# uC.net
KiCad netlist of a schematic drawn in Altium Designer
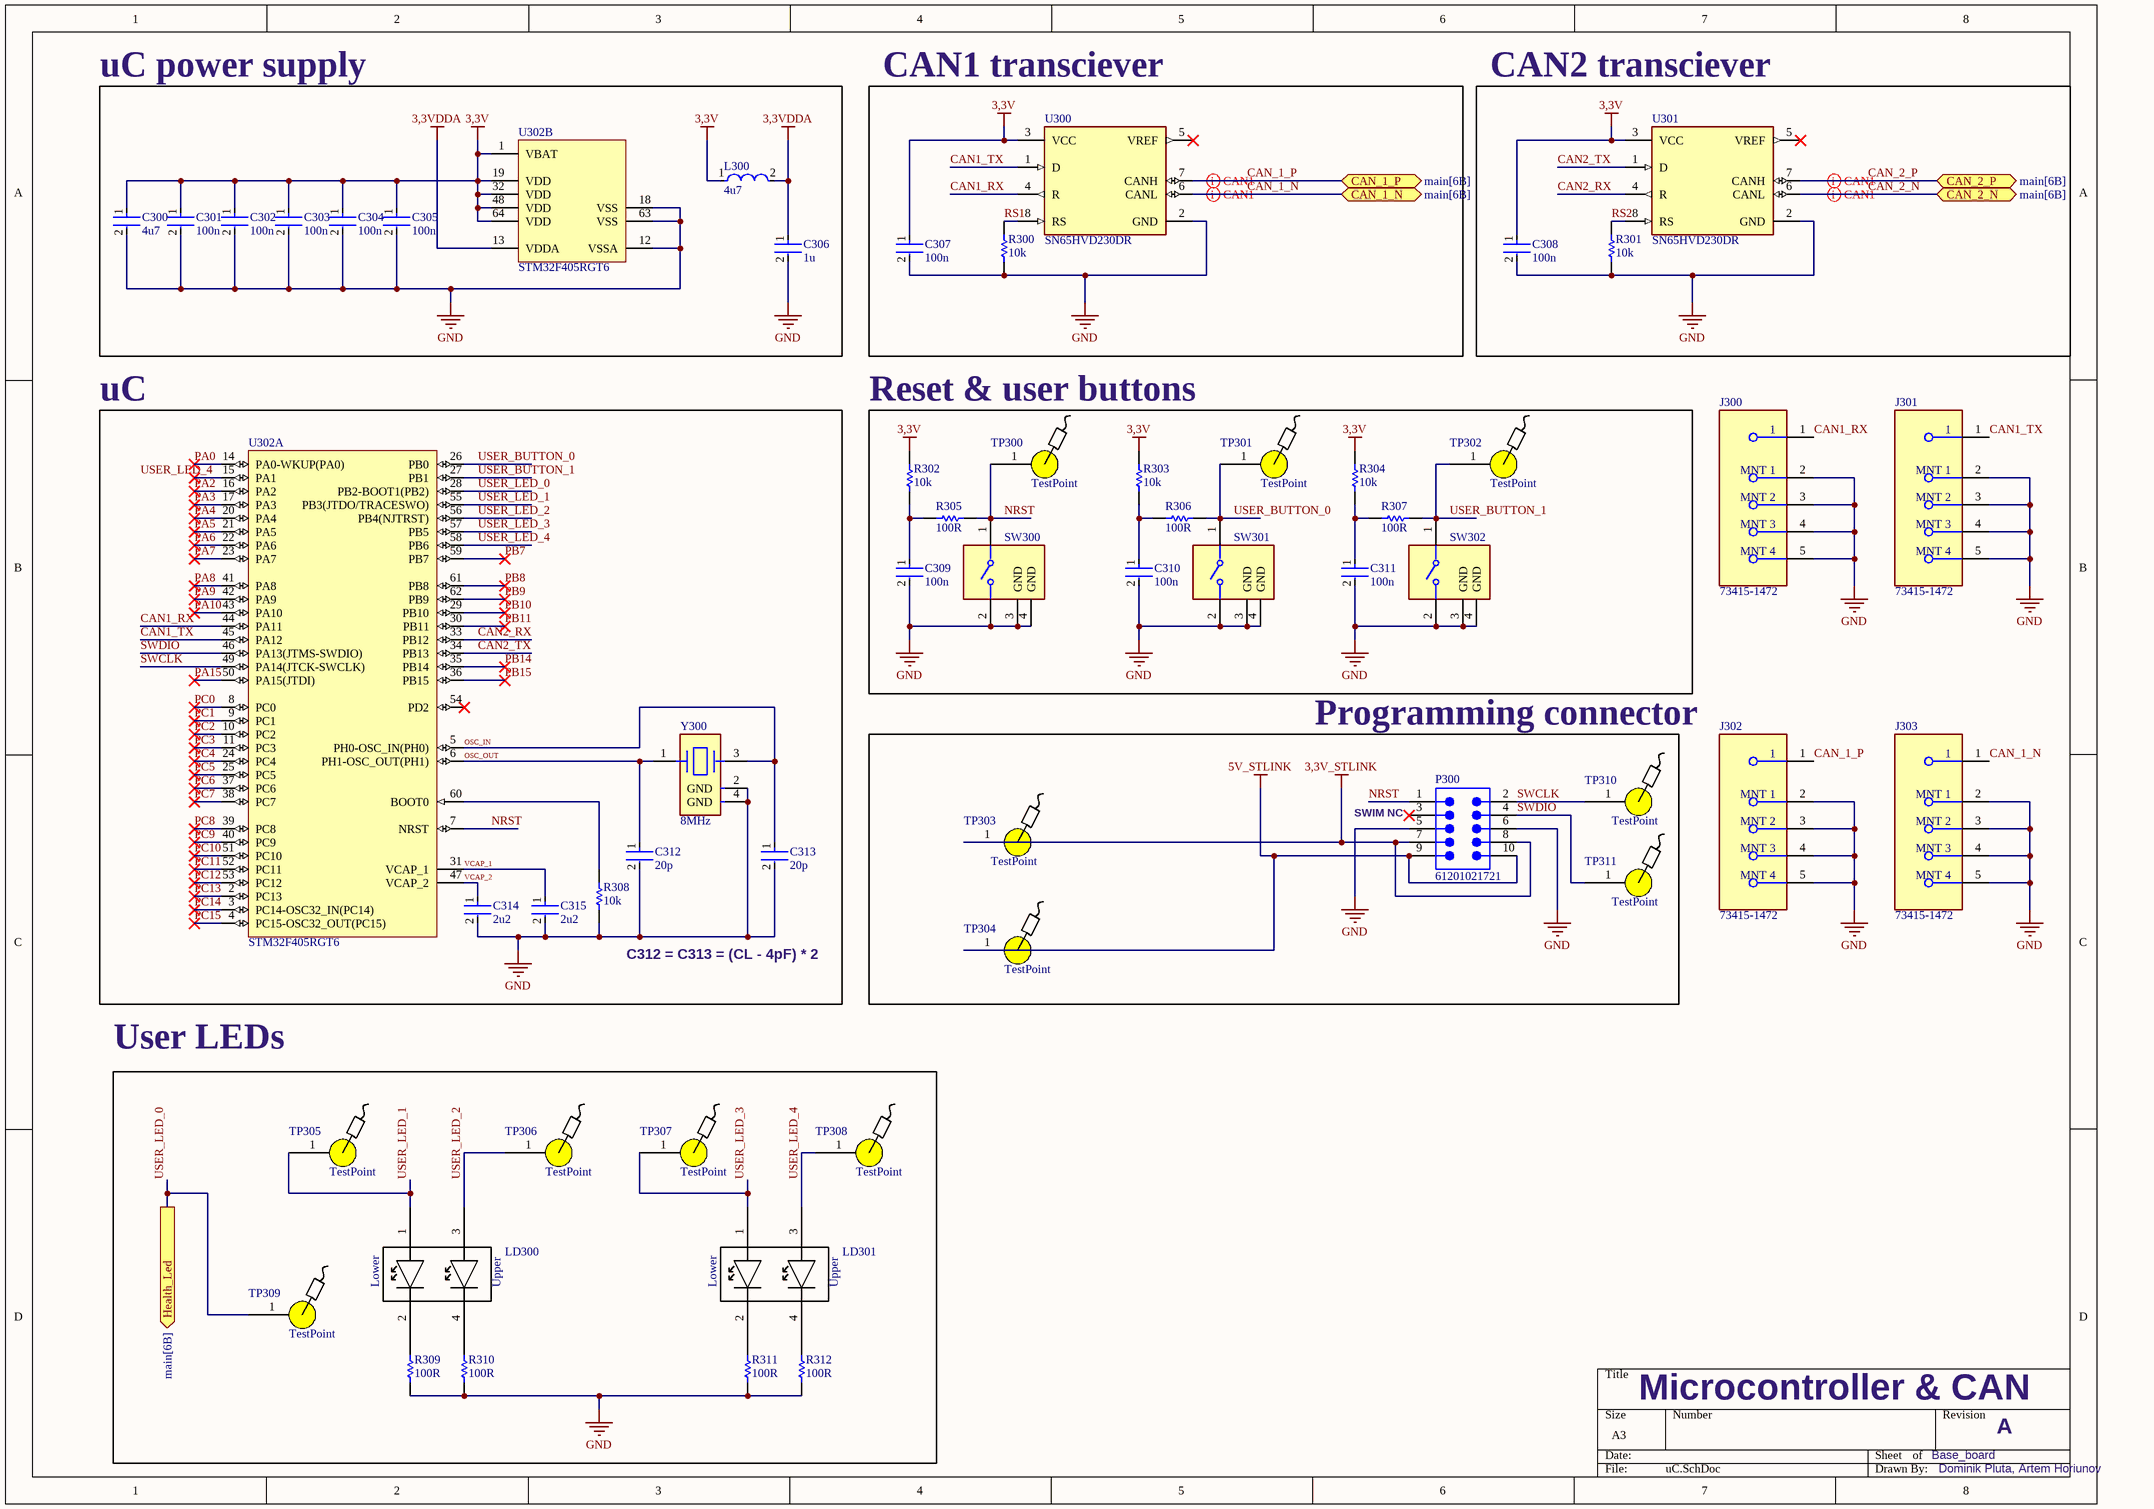
[diagram p0: uC.SchDoc]

(export (version "E")
  (design (tool "Eeschema 10.0.6"))
  (components
    (comp (ref "C300")
      (value "4u7")
      (footprint "FP-C0603C-CF-MFG")
      (description "CAP CER 0.1UF 50V X7R 0603")
      (fields (field (name "TOLERANCE") "0.1") (field (name "MANUFACTURER") "KEMET"))
      (libsource (lib "Altium Content Vault") (part "b4654b650e69147ec39a6b967a45e02"))
    )
    (comp (ref "C301")
      (value "100n")
      (footprint "FP-C0603C-CF-MFG")
      (description "CAP CER 0.1UF 50V X7R 0603")
      (fields (field (name "TOLERANCE") "0.1") (field (name "MANUFACTURER") "KEMET"))
      (libsource (lib "Altium Content Vault") (part "b4654b650e69147ec39a6b967a45e02"))
    )
    (comp (ref "C302")
      (value "100n")
      (footprint "FP-C0603C-CF-MFG")
      (description "CAP CER 0.1UF 50V X7R 0603")
      (fields (field (name "TOLERANCE") "0.1") (field (name "MANUFACTURER") "KEMET"))
      (libsource (lib "Altium Content Vault") (part "b4654b650e69147ec39a6b967a45e02"))
    )
    (comp (ref "C303")
      (value "100n")
      (footprint "FP-C0603C-CF-MFG")
      (description "CAP CER 0.1UF 50V X7R 0603")
      (fields (field (name "TOLERANCE") "0.1") (field (name "MANUFACTURER") "KEMET"))
      (libsource (lib "Altium Content Vault") (part "b4654b650e69147ec39a6b967a45e02"))
    )
    (comp (ref "C304")
      (value "100n")
      (footprint "FP-C0603C-CF-MFG")
      (description "CAP CER 0.1UF 50V X7R 0603")
      (fields (field (name "TOLERANCE") "0.1") (field (name "MANUFACTURER") "KEMET"))
      (libsource (lib "Altium Content Vault") (part "b4654b650e69147ec39a6b967a45e02"))
    )
    (comp (ref "C305")
      (value "100n")
      (footprint "FP-C0603C-CF-MFG")
      (description "CAP CER 0.1UF 50V X7R 0603")
      (fields (field (name "TOLERANCE") "0.1") (field (name "MANUFACTURER") "KEMET"))
      (libsource (lib "Altium Content Vault") (part "b4654b650e69147ec39a6b967a45e02"))
    )
    (comp (ref "C306")
      (value "1u")
      (footprint "FP-C0603C-CF-MFG")
      (description "CAP CER 0.1UF 50V X7R 0603")
      (fields (field (name "TOLERANCE") "0.1") (field (name "MANUFACTURER") "KEMET"))
      (libsource (lib "Altium Content Vault") (part "b4654b650e69147ec39a6b967a45e02"))
    )
    (comp (ref "C307")
      (value "100n")
      (footprint "FP-C0603C-CF-MFG")
      (description "CAP CER 0.1UF 50V X7R 0603")
      (fields (field (name "TOLERANCE") "0.1") (field (name "MANUFACTURER") "KEMET"))
      (libsource (lib "Altium Content Vault") (part "b4654b650e69147ec39a6b967a45e02"))
    )
    (comp (ref "C308")
      (value "100n")
      (footprint "FP-C0603C-CF-MFG")
      (description "CAP CER 0.1UF 50V X7R 0603")
      (fields (field (name "TOLERANCE") "0.1") (field (name "MANUFACTURER") "KEMET"))
      (libsource (lib "Altium Content Vault") (part "b4654b650e69147ec39a6b967a45e02"))
    )
    (comp (ref "C309")
      (value "100n")
      (footprint "FP-C0603C-CF-MFG")
      (description "CAP CER 0.1UF 50V X7R 0603")
      (fields (field (name "TOLERANCE") "0.1") (field (name "MANUFACTURER") "KEMET"))
      (libsource (lib "Altium Content Vault") (part "b4654b650e69147ec39a6b967a45e02"))
    )
    (comp (ref "C310")
      (value "100n")
      (footprint "FP-C0603C-CF-MFG")
      (description "CAP CER 0.1UF 50V X7R 0603")
      (fields (field (name "TOLERANCE") "0.1") (field (name "MANUFACTURER") "KEMET"))
      (libsource (lib "Altium Content Vault") (part "b4654b650e69147ec39a6b967a45e02"))
    )
    (comp (ref "C311")
      (value "100n")
      (footprint "FP-C0603C-CF-MFG")
      (description "CAP CER 0.1UF 50V X7R 0603")
      (fields (field (name "TOLERANCE") "0.1") (field (name "MANUFACTURER") "KEMET"))
      (libsource (lib "Altium Content Vault") (part "b4654b650e69147ec39a6b967a45e02"))
    )
    (comp (ref "C312")
      (value "20p")
      (footprint "FP-C0603C-CF-MFG")
      (description "CAP CER 50V X7R 0603")
      (fields (field (name "TOLERANCE") "0.1") (field (name "MANUFACTURER") "KEMET"))
      (libsource (lib "Altium Content Vault") (part "b4654b650e69147ec39a6b967a45e02"))
    )
    (comp (ref "C313")
      (value "20p")
      (footprint "FP-C0603C-CF-MFG")
      (description "CAP CER 50V X7R 0603")
      (fields (field (name "TOLERANCE") "0.1") (field (name "MANUFACTURER") "KEMET"))
      (libsource (lib "Altium Content Vault") (part "b4654b650e69147ec39a6b967a45e02"))
    )
    (comp (ref "C314")
      (value "2u2")
      (footprint "FP-C0603C-CF-MFG")
      (description "CAP CER 50V X7R 0603")
      (fields (field (name "TOLERANCE") "0.1") (field (name "MANUFACTURER") "KEMET"))
      (libsource (lib "Altium Content Vault") (part "b4654b650e69147ec39a6b967a45e02"))
    )
    (comp (ref "C315")
      (value "2u2")
      (footprint "FP-C0603C-CF-MFG")
      (description "CAP CER 50V X7R 0603")
      (fields (field (name "TOLERANCE") "0.1") (field (name "MANUFACTURER") "KEMET"))
      (libsource (lib "Altium Content Vault") (part "b4654b650e69147ec39a6b967a45e02"))
    )
    (comp (ref "J300")
      (value "73415-1472")
      (footprint "FP-73415-1472-MFG")
      (libsource (lib "Altium Content Vault") (part "c65b8a639cdaef1819ea20b5466f8fa"))
    )
    (comp (ref "J301")
      (value "73415-1472")
      (footprint "FP-73415-1472-MFG")
      (libsource (lib "Altium Content Vault") (part "c65b8a639cdaef1819ea20b5466f8fa"))
    )
    (comp (ref "J302")
      (value "73415-1472")
      (footprint "FP-73415-1472-MFG")
      (libsource (lib "Altium Content Vault") (part "c65b8a639cdaef1819ea20b5466f8fa"))
    )
    (comp (ref "J303")
      (value "73415-1472")
      (footprint "FP-73415-1472-MFG")
      (libsource (lib "Altium Content Vault") (part "c65b8a639cdaef1819ea20b5466f8fa"))
    )
    (comp (ref "L300")
      (value "4u7")
      (footprint "FP-LQM21DN_00-MFG")
      (description "Multilayer Type Inductor for General Circuits, 0805 (2012), 0.22μH, 10%, 0.38Ω, 250mA")
      (fields (field (name "TOLERANCE") "10%"))
      (libsource (lib "Altium Content Vault") (part "725321dda6339637d4d059423bc1c3c"))
    )
    (comp (ref "LD300")
      (value "~")
      (footprint "LedHolder:LED_HOLDER")
      (libsource (lib "LedHolder") (part "DoubleStack_Side_Led_3mm"))
    )
    (comp (ref "LD301")
      (value "~")
      (footprint "LedHolder:LED_HOLDER")
      (libsource (lib "LedHolder") (part "DoubleStack_Side_Led_3mm"))
    )
    (comp (ref "P300")
      (value "61201021721")
      (footprint "61201021721")
      (libsource (lib "Altium Content Vault") (part "Header_Male_2R_10P"))
    )
    (comp (ref "R300")
      (value "10k")
      (footprint "RESC0603(1608)_N")
      (description "2K 0.1W 5% 0603 (1608 Metric)  SMD")
      (fields (field (name "TOLERANCE") "5 %") (field (name "POWER") "0.1 W"))
      (libsource (lib "Altium Content Vault") (part "RES"))
    )
    (comp (ref "R301")
      (value "10k")
      (footprint "RESC0603(1608)_N")
      (description "2K 0.1W 5% 0603 (1608 Metric)  SMD")
      (fields (field (name "TOLERANCE") "5 %") (field (name "POWER") "0.1 W"))
      (libsource (lib "Altium Content Vault") (part "RES"))
    )
    (comp (ref "R302")
      (value "10k")
      (footprint "RESC0603(1608)_N")
      (description "0.1W 5% 0603 (1608 Metric)  SMD")
      (fields (field (name "TOLERANCE") "5 %") (field (name "POWER") "0.1 W"))
      (libsource (lib "Altium Content Vault") (part "RES"))
    )
    (comp (ref "R303")
      (value "10k")
      (footprint "RESC0603(1608)_N")
      (description "0.1W 5% 0603 (1608 Metric)  SMD")
      (fields (field (name "TOLERANCE") "5 %") (field (name "POWER") "0.1 W"))
      (libsource (lib "Altium Content Vault") (part "RES"))
    )
    (comp (ref "R304")
      (value "10k")
      (footprint "RESC0603(1608)_N")
      (description "0.1W 5% 0603 (1608 Metric)  SMD")
      (fields (field (name "TOLERANCE") "5 %") (field (name "POWER") "0.1 W"))
      (libsource (lib "Altium Content Vault") (part "RES"))
    )
    (comp (ref "R305")
      (value "100R")
      (footprint "RESC0603(1608)_N")
      (description "0.1W 5% 0603 (1608 Metric)  SMD")
      (fields (field (name "TOLERANCE") "5 %") (field (name "POWER") "0.1 W"))
      (libsource (lib "Altium Content Vault") (part "RES"))
    )
    (comp (ref "R306")
      (value "100R")
      (footprint "RESC0603(1608)_N")
      (description "0.1W 5% 0603 (1608 Metric)  SMD")
      (fields (field (name "TOLERANCE") "5 %") (field (name "POWER") "0.1 W"))
      (libsource (lib "Altium Content Vault") (part "RES"))
    )
    (comp (ref "R307")
      (value "100R")
      (footprint "RESC0603(1608)_N")
      (description "0.1W 5% 0603 (1608 Metric)  SMD")
      (fields (field (name "TOLERANCE") "5 %") (field (name "POWER") "0.1 W"))
      (libsource (lib "Altium Content Vault") (part "RES"))
    )
    (comp (ref "R308")
      (value "10k")
      (footprint "RESC0603(1608)_N")
      (description "2K 0.1W 5% 0603 (1608 Metric)  SMD")
      (fields (field (name "TOLERANCE") "5 %") (field (name "POWER") "0.1 W"))
      (libsource (lib "Altium Content Vault") (part "RES"))
    )
    (comp (ref "R309")
      (value "100R")
      (footprint "RESC0603(1608)_N")
      (description "0.1W 1% 0603 (1608 Metric)  SMD")
      (fields (field (name "TOLERANCE") "5 %") (field (name "POWER") "0.1 W"))
      (libsource (lib "Altium Content Vault") (part "RES"))
    )
    (comp (ref "R310")
      (value "100R")
      (footprint "RESC0603(1608)_N")
      (description "0.1W 1% 0603 (1608 Metric)  SMD")
      (fields (field (name "TOLERANCE") "5 %") (field (name "POWER") "0.1 W"))
      (libsource (lib "Altium Content Vault") (part "RES"))
    )
    (comp (ref "R311")
      (value "100R")
      (footprint "RESC0603(1608)_N")
      (description "0.1W 1% 0603 (1608 Metric)  SMD")
      (fields (field (name "TOLERANCE") "5 %") (field (name "POWER") "0.1 W"))
      (libsource (lib "Altium Content Vault") (part "RES"))
    )
    (comp (ref "R312")
      (value "100R")
      (footprint "RESC0603(1608)_N")
      (description "0.1W 1% 0603 (1608 Metric)  SMD")
      (fields (field (name "TOLERANCE") "5 %") (field (name "POWER") "0.1 W"))
      (libsource (lib "Altium Content Vault") (part "RES"))
    )
    (comp (ref "SW300")
      (value "B3F-3122")
      (footprint "FP-B3F-3122-MFG")
      (description "SWITCH TACTILE SPST-NO 0.05A 24V")
      (libsource (lib "Altium Content Vault") (part "05c531d4b500f7e9514fa3f65f375ae"))
    )
    (comp (ref "SW301")
      (value "B3F-3122")
      (footprint "FP-B3F-3122-MFG")
      (description "SWITCH TACTILE SPST-NO 0.05A 24V")
      (libsource (lib "Altium Content Vault") (part "05c531d4b500f7e9514fa3f65f375ae"))
    )
    (comp (ref "SW302")
      (value "B3F-3122")
      (footprint "FP-B3F-3122-MFG")
      (description "SWITCH TACTILE SPST-NO 0.05A 24V")
      (libsource (lib "Altium Content Vault") (part "05c531d4b500f7e9514fa3f65f375ae"))
    )
    (comp (ref "TP300")
      (value "TestPoint")
      (footprint "TestPoint")
      (libsource (lib "TestPoint") (part "TestPoint"))
    )
    (comp (ref "TP301")
      (value "TestPoint")
      (footprint "TestPoint")
      (libsource (lib "TestPoint") (part "TestPoint"))
    )
    (comp (ref "TP302")
      (value "TestPoint")
      (footprint "TestPoint")
      (libsource (lib "TestPoint") (part "TestPoint"))
    )
    (comp (ref "TP303")
      (value "TestPoint")
      (footprint "TestPoint")
      (libsource (lib "TestPoint") (part "TestPoint"))
    )
    (comp (ref "TP304")
      (value "TestPoint")
      (footprint "TestPoint")
      (libsource (lib "TestPoint") (part "TestPoint"))
    )
    (comp (ref "TP305")
      (value "TestPoint")
      (footprint "TestPoint")
      (libsource (lib "TestPoint") (part "TestPoint"))
    )
    (comp (ref "TP306")
      (value "TestPoint")
      (footprint "TestPoint")
      (libsource (lib "TestPoint") (part "TestPoint"))
    )
    (comp (ref "TP307")
      (value "TestPoint")
      (footprint "TestPoint")
      (libsource (lib "TestPoint") (part "TestPoint"))
    )
    (comp (ref "TP308")
      (value "TestPoint")
      (footprint "TestPoint")
      (libsource (lib "TestPoint") (part "TestPoint"))
    )
    (comp (ref "TP309")
      (value "TestPoint")
      (footprint "TestPoint")
      (libsource (lib "TestPoint") (part "TestPoint"))
    )
    (comp (ref "TP310")
      (value "TestPoint")
      (footprint "TestPoint")
      (libsource (lib "TestPoint") (part "TestPoint"))
    )
    (comp (ref "TP311")
      (value "TestPoint")
      (footprint "TestPoint")
      (libsource (lib "TestPoint") (part "TestPoint"))
    )
    (comp (ref "U300")
      (value "SN65HVD230DR")
      (footprint "FP-D0008A-IPC_A")
      (description "IC TRANSCEIVER HALF 1/1 8SOIC")
      (libsource (lib "Altium Content Vault") (part "43b56812b1adf0e60a7acfb7c27ab91"))
    )
    (comp (ref "U301")
      (value "SN65HVD230DR")
      (footprint "FP-D0008A-IPC_A")
      (description "IC TRANSCEIVER HALF 1/1 8SOIC")
      (libsource (lib "Altium Content Vault") (part "43b56812b1adf0e60a7acfb7c27ab91"))
    )
    (comp (ref "U302")
      (value "STM32F405RGT6")
      (footprint "STM-LQFP64_M")
      (fields (field (name "MANUFACTURER") "STMicroelectronics"))
      (libsource (lib "Altium Content Vault") (part "MC-ARM-STM32F4X5-SQ64"))
    )
    (comp (ref "Y300")
      (value "8MHz")
      (footprint "FP-7M-MFG")
      (description "Crystal")
      (fields (field (name "TOLERANCE") "10ppm"))
      (libsource (lib "Altium Content Vault") (part "41079aabb0e87794b56622915be14ed"))
    )
  )
  (nets
    (net (code "2") (name "/CAN1_RX") (class "Default")
      (node (ref "J300") (pin "1") (pinfunction "1_1") (pintype "passive"))
      (node (ref "U300") (pin "4") (pinfunction "R_4") (pintype "output"))
      (node (ref "U302") (pin "44") (pinfunction "PA11_44") (pintype "bidirectional"))
    )
    (net (code "3") (name "/CAN1_TX") (class "Default")
      (node (ref "J301") (pin "1") (pinfunction "1_1") (pintype "passive"))
      (node (ref "U300") (pin "1") (pinfunction "D_1") (pintype "input"))
      (node (ref "U302") (pin "45") (pinfunction "PA12_45") (pintype "bidirectional"))
    )
    (net (code "4") (name "/CAN2_RX") (class "Default")
      (node (ref "U301") (pin "4") (pinfunction "R_4") (pintype "output"))
      (node (ref "U302") (pin "33") (pinfunction "PB12_33") (pintype "bidirectional"))
    )
    (net (code "5") (name "/CAN2_TX") (class "Default")
      (node (ref "U301") (pin "1") (pinfunction "D_1") (pintype "input"))
      (node (ref "U302") (pin "34") (pinfunction "PB13_34") (pintype "bidirectional"))
    )
    (net (code "6") (name "/CAN_1_N") (class "Default")
      (node (ref "J303") (pin "1") (pinfunction "1_1") (pintype "passive"))
      (node (ref "U300") (pin "6") (pinfunction "CANL_6") (pintype "bidirectional"))
    )
    (net (code "7") (name "/CAN_1_P") (class "Default")
      (node (ref "J302") (pin "1") (pinfunction "1_1") (pintype "passive"))
      (node (ref "U300") (pin "7") (pinfunction "CANH_7") (pintype "bidirectional"))
    )
    (net (code "8") (name "/CAN_2_N") (class "Default")
      (node (ref "U301") (pin "6") (pinfunction "CANL_6") (pintype "bidirectional"))
    )
    (net (code "9") (name "/CAN_2_P") (class "Default")
      (node (ref "U301") (pin "7") (pinfunction "CANH_7") (pintype "bidirectional"))
    )
    (net (code "10") (name "/NRST") (class "Default")
      (node (ref "P300") (pin "1") (pinfunction "1_1") (pintype "passive"))
      (node (ref "R305") (pin "1") (pinfunction "1_1") (pintype "passive"))
      (node (ref "SW300") (pin "1") (pinfunction "1_1") (pintype "passive"))
      (node (ref "TP300") (pin "1") (pintype "passive"))
      (node (ref "U302") (pin "7") (pinfunction "NRST_7") (pintype "bidirectional"))
    )
    (net (code "11") (name "/OSC_IN") (class "Default")
      (node (ref "C313") (pin "1") (pinfunction "1_1") (pintype "passive"))
      (node (ref "U302") (pin "5") (pinfunction "PH0-OSC_IN(PH0)_5") (pintype "bidirectional"))
      (node (ref "Y300") (pin "3") (pinfunction "3_3") (pintype "passive"))
    )
    (net (code "12") (name "/OSC_OUT") (class "Default")
      (node (ref "C312") (pin "1") (pinfunction "1_1") (pintype "passive"))
      (node (ref "U302") (pin "6") (pinfunction "PH1-OSC_OUT(PH1)_6") (pintype "bidirectional"))
      (node (ref "Y300") (pin "1") (pinfunction "1_1") (pintype "passive"))
    )
    (net (code "13") (name "/PA0") (class "Default")
      (node (ref "U302") (pin "14") (pinfunction "PA0-WKUP(PA0)_14") (pintype "bidirectional+no_connect"))
    )
    (net (code "14") (name "/PA2") (class "Default")
      (node (ref "U302") (pin "16") (pinfunction "PA2_16") (pintype "bidirectional+no_connect"))
    )
    (net (code "15") (name "/PA3") (class "Default")
      (node (ref "U302") (pin "17") (pinfunction "PA3_17") (pintype "bidirectional+no_connect"))
    )
    (net (code "16") (name "/PA4") (class "Default")
      (node (ref "U302") (pin "20") (pinfunction "PA4_20") (pintype "bidirectional+no_connect"))
    )
    (net (code "17") (name "/PA5") (class "Default")
      (node (ref "U302") (pin "21") (pinfunction "PA5_21") (pintype "bidirectional+no_connect"))
    )
    (net (code "18") (name "/PA6") (class "Default")
      (node (ref "U302") (pin "22") (pinfunction "PA6_22") (pintype "bidirectional+no_connect"))
    )
    (net (code "19") (name "/PA7") (class "Default")
      (node (ref "U302") (pin "23") (pinfunction "PA7_23") (pintype "bidirectional+no_connect"))
    )
    (net (code "20") (name "/PA8") (class "Default")
      (node (ref "U302") (pin "41") (pinfunction "PA8_41") (pintype "bidirectional+no_connect"))
    )
    (net (code "21") (name "/PA9") (class "Default")
      (node (ref "U302") (pin "42") (pinfunction "PA9_42") (pintype "bidirectional+no_connect"))
    )
    (net (code "22") (name "/PA10") (class "Default")
      (node (ref "U302") (pin "43") (pinfunction "PA10_43") (pintype "bidirectional+no_connect"))
    )
    (net (code "23") (name "/PA15") (class "Default")
      (node (ref "U302") (pin "50") (pinfunction "PA15(JTDI)_50") (pintype "bidirectional+no_connect"))
    )
    (net (code "24") (name "/PB7") (class "Default")
      (node (ref "U302") (pin "59") (pinfunction "PB7_59") (pintype "bidirectional+no_connect"))
    )
    (net (code "25") (name "/PB8") (class "Default")
      (node (ref "U302") (pin "61") (pinfunction "PB8_61") (pintype "bidirectional+no_connect"))
    )
    (net (code "26") (name "/PB9") (class "Default")
      (node (ref "U302") (pin "62") (pinfunction "PB9_62") (pintype "bidirectional+no_connect"))
    )
    (net (code "27") (name "/PB10") (class "Default")
      (node (ref "U302") (pin "29") (pinfunction "PB10_29") (pintype "bidirectional+no_connect"))
    )
    (net (code "28") (name "/PB11") (class "Default")
      (node (ref "U302") (pin "30") (pinfunction "PB11_30") (pintype "bidirectional+no_connect"))
    )
    (net (code "29") (name "/PB14") (class "Default")
      (node (ref "U302") (pin "35") (pinfunction "PB14_35") (pintype "bidirectional+no_connect"))
    )
    (net (code "30") (name "/PB15") (class "Default")
      (node (ref "U302") (pin "36") (pinfunction "PB15_36") (pintype "bidirectional+no_connect"))
    )
    (net (code "31") (name "/PC0") (class "Default")
      (node (ref "U302") (pin "8") (pinfunction "PC0_8") (pintype "bidirectional+no_connect"))
    )
    (net (code "32") (name "/PC1") (class "Default")
      (node (ref "U302") (pin "9") (pinfunction "PC1_9") (pintype "bidirectional+no_connect"))
    )
    (net (code "33") (name "/PC2") (class "Default")
      (node (ref "U302") (pin "10") (pinfunction "PC2_10") (pintype "bidirectional+no_connect"))
    )
    (net (code "34") (name "/PC3") (class "Default")
      (node (ref "U302") (pin "11") (pinfunction "PC3_11") (pintype "bidirectional+no_connect"))
    )
    (net (code "35") (name "/PC4") (class "Default")
      (node (ref "U302") (pin "24") (pinfunction "PC4_24") (pintype "bidirectional+no_connect"))
    )
    (net (code "36") (name "/PC5") (class "Default")
      (node (ref "U302") (pin "25") (pinfunction "PC5_25") (pintype "bidirectional+no_connect"))
    )
    (net (code "37") (name "/PC6") (class "Default")
      (node (ref "U302") (pin "37") (pinfunction "PC6_37") (pintype "bidirectional+no_connect"))
    )
    (net (code "38") (name "/PC7") (class "Default")
      (node (ref "U302") (pin "38") (pinfunction "PC7_38") (pintype "bidirectional+no_connect"))
    )
    (net (code "39") (name "/PC8") (class "Default")
      (node (ref "U302") (pin "39") (pinfunction "PC8_39") (pintype "bidirectional+no_connect"))
    )
    (net (code "40") (name "/PC9") (class "Default")
      (node (ref "U302") (pin "40") (pinfunction "PC9_40") (pintype "bidirectional+no_connect"))
    )
    (net (code "41") (name "/PC10") (class "Default")
      (node (ref "U302") (pin "51") (pinfunction "PC10_51") (pintype "bidirectional+no_connect"))
    )
    (net (code "42") (name "/PC11") (class "Default")
      (node (ref "U302") (pin "52") (pinfunction "PC11_52") (pintype "bidirectional+no_connect"))
    )
    (net (code "43") (name "/PC12") (class "Default")
      (node (ref "U302") (pin "53") (pinfunction "PC12_53") (pintype "bidirectional+no_connect"))
    )
    (net (code "44") (name "/PC13") (class "Default")
      (node (ref "U302") (pin "2") (pinfunction "PC13_2") (pintype "bidirectional+no_connect"))
    )
    (net (code "45") (name "/PC14") (class "Default")
      (node (ref "U302") (pin "3") (pinfunction "PC14-OSC32_IN(PC14)_3") (pintype "bidirectional+no_connect"))
    )
    (net (code "46") (name "/PC15") (class "Default")
      (node (ref "U302") (pin "4") (pinfunction "PC15-OSC32_OUT(PC15)_4") (pintype "bidirectional+no_connect"))
    )
    (net (code "47") (name "/RS1") (class "Default")
      (node (ref "R300") (pin "2") (pinfunction "2_2") (pintype "passive"))
      (node (ref "U300") (pin "8") (pinfunction "RS_8") (pintype "input"))
    )
    (net (code "48") (name "/RS2") (class "Default")
      (node (ref "R301") (pin "2") (pinfunction "2_2") (pintype "passive"))
      (node (ref "U301") (pin "8") (pinfunction "RS_8") (pintype "input"))
    )
    (net (code "49") (name "/SWCLK") (class "Default")
      (node (ref "P300") (pin "2") (pinfunction "2_2") (pintype "passive"))
      (node (ref "TP310") (pin "1") (pintype "passive"))
      (node (ref "U302") (pin "49") (pinfunction "PA14(JTCK-SWCLK)_49") (pintype "bidirectional"))
    )
    (net (code "50") (name "/SWDIO") (class "Default")
      (node (ref "P300") (pin "4") (pinfunction "4_4") (pintype "passive"))
      (node (ref "TP311") (pin "1") (pintype "passive"))
      (node (ref "U302") (pin "46") (pinfunction "PA13(JTMS-SWDIO)_46") (pintype "bidirectional"))
    )
    (net (code "51") (name "/USER_BUTTON_0") (class "Default")
      (node (ref "R306") (pin "1") (pinfunction "1_1") (pintype "passive"))
      (node (ref "SW301") (pin "1") (pinfunction "1_1") (pintype "passive"))
      (node (ref "TP301") (pin "1") (pintype "passive"))
      (node (ref "U302") (pin "26") (pinfunction "PB0_26") (pintype "bidirectional"))
    )
    (net (code "52") (name "/USER_BUTTON_1") (class "Default")
      (node (ref "R307") (pin "1") (pinfunction "1_1") (pintype "passive"))
      (node (ref "SW302") (pin "1") (pinfunction "1_1") (pintype "passive"))
      (node (ref "TP302") (pin "1") (pintype "passive"))
      (node (ref "U302") (pin "27") (pinfunction "PB1_27") (pintype "bidirectional"))
    )
    (net (code "53") (name "/USER_LED_0") (class "Default")
      (node (ref "TP309") (pin "1") (pintype "passive"))
      (node (ref "U302") (pin "28") (pinfunction "PB2-BOOT1(PB2)_28") (pintype "bidirectional"))
    )
    (net (code "54") (name "/USER_LED_1") (class "Default")
      (node (ref "LD300") (pin "1") (pintype "passive"))
      (node (ref "TP305") (pin "1") (pintype "passive"))
      (node (ref "U302") (pin "55") (pinfunction "PB3(JTDO/TRACESWO)_55") (pintype "bidirectional"))
    )
    (net (code "55") (name "/USER_LED_2") (class "Default")
      (node (ref "LD300") (pin "3") (pintype "passive"))
      (node (ref "TP306") (pin "1") (pintype "passive"))
      (node (ref "U302") (pin "56") (pinfunction "PB4(NJTRST)_56") (pintype "bidirectional"))
    )
    (net (code "56") (name "/USER_LED_3") (class "Default")
      (node (ref "LD301") (pin "1") (pintype "passive"))
      (node (ref "TP307") (pin "1") (pintype "passive"))
      (node (ref "U302") (pin "57") (pinfunction "PB5_57") (pintype "bidirectional"))
    )
    (net (code "57") (name "/USER_LED_4") (class "Default")
      (node (ref "LD301") (pin "3") (pintype "passive"))
      (node (ref "TP308") (pin "1") (pintype "passive"))
      (node (ref "U302") (pin "58") (pinfunction "PB6_58") (pintype "bidirectional"))
    )
    (net (code "58") (name "/VCAP_1") (class "Default")
      (node (ref "C315") (pin "1") (pinfunction "1_1") (pintype "passive"))
      (node (ref "U302") (pin "31") (pinfunction "VCAP_1_31") (pintype "power_in"))
    )
    (net (code "59") (name "/VCAP_2") (class "Default")
      (node (ref "C314") (pin "1") (pinfunction "1_1") (pintype "passive"))
      (node (ref "U302") (pin "47") (pinfunction "VCAP_2_47") (pintype "power_in"))
    )
    (net (code "60") (name "3,3V") (class "Default")
      (node (ref "C300") (pin "1") (pinfunction "1_1") (pintype "passive"))
      (node (ref "C301") (pin "1") (pinfunction "1_1") (pintype "passive"))
      (node (ref "C302") (pin "1") (pinfunction "1_1") (pintype "passive"))
      (node (ref "C303") (pin "1") (pinfunction "1_1") (pintype "passive"))
      (node (ref "C304") (pin "1") (pinfunction "1_1") (pintype "passive"))
      (node (ref "C305") (pin "1") (pinfunction "1_1") (pintype "passive"))
      (node (ref "C307") (pin "1") (pinfunction "1_1") (pintype "passive"))
      (node (ref "C308") (pin "1") (pinfunction "1_1") (pintype "passive"))
      (node (ref "L300") (pin "1") (pinfunction "1_1") (pintype "passive"))
      (node (ref "R302") (pin "2") (pinfunction "2_2") (pintype "passive"))
      (node (ref "R303") (pin "2") (pinfunction "2_2") (pintype "passive"))
      (node (ref "R304") (pin "2") (pinfunction "2_2") (pintype "passive"))
      (node (ref "U300") (pin "3") (pinfunction "VCC_3") (pintype "power_in"))
      (node (ref "U301") (pin "3") (pinfunction "VCC_3") (pintype "power_in"))
      (node (ref "U302") (pin "1") (pinfunction "VBAT_1") (pintype "power_in"))
      (node (ref "U302") (pin "19") (pinfunction "VDD_19") (pintype "power_in"))
      (node (ref "U302") (pin "32") (pinfunction "VDD_32") (pintype "power_in"))
      (node (ref "U302") (pin "48") (pinfunction "VDD_48") (pintype "power_in"))
      (node (ref "U302") (pin "64") (pinfunction "VDD_64") (pintype "power_in"))
    )
    (net (code "61") (name "3,3VDDA") (class "Default")
      (node (ref "C306") (pin "1") (pinfunction "1_1") (pintype "passive"))
      (node (ref "L300") (pin "2") (pinfunction "2_2") (pintype "passive"))
      (node (ref "U302") (pin "13") (pinfunction "VDDA_13") (pintype "power_in"))
    )
    (net (code "62") (name "3,3V_STLINK") (class "Default")
      (node (ref "P300") (pin "7") (pinfunction "7_7") (pintype "passive"))
      (node (ref "P300") (pin "8") (pinfunction "8_8") (pintype "passive"))
      (node (ref "TP303") (pin "1") (pintype "passive"))
    )
    (net (code "63") (name "5V_STLINK") (class "Default")
      (node (ref "P300") (pin "10") (pinfunction "10_10") (pintype "passive"))
      (node (ref "P300") (pin "9") (pinfunction "9_9") (pintype "passive"))
      (node (ref "TP304") (pin "1") (pintype "passive"))
    )
    (net (code "64") (name "GND") (class "Default")
      (node (ref "C300") (pin "2") (pinfunction "2_2") (pintype "passive"))
      (node (ref "C301") (pin "2") (pinfunction "2_2") (pintype "passive"))
      (node (ref "C302") (pin "2") (pinfunction "2_2") (pintype "passive"))
      (node (ref "C303") (pin "2") (pinfunction "2_2") (pintype "passive"))
      (node (ref "C304") (pin "2") (pinfunction "2_2") (pintype "passive"))
      (node (ref "C305") (pin "2") (pinfunction "2_2") (pintype "passive"))
      (node (ref "C306") (pin "2") (pinfunction "2_2") (pintype "passive"))
      (node (ref "C307") (pin "2") (pinfunction "2_2") (pintype "passive"))
      (node (ref "C308") (pin "2") (pinfunction "2_2") (pintype "passive"))
      (node (ref "C309") (pin "2") (pinfunction "2_2") (pintype "passive"))
      (node (ref "C310") (pin "2") (pinfunction "2_2") (pintype "passive"))
      (node (ref "C311") (pin "2") (pinfunction "2_2") (pintype "passive"))
      (node (ref "C312") (pin "2") (pinfunction "2_2") (pintype "passive"))
      (node (ref "C313") (pin "2") (pinfunction "2_2") (pintype "passive"))
      (node (ref "C314") (pin "2") (pinfunction "2_2") (pintype "passive"))
      (node (ref "C315") (pin "2") (pinfunction "2_2") (pintype "passive"))
      (node (ref "J300") (pin "2") (pinfunction "MNT_1_2") (pintype "passive"))
      (node (ref "J300") (pin "3") (pinfunction "MNT_2_3") (pintype "passive"))
      (node (ref "J300") (pin "4") (pinfunction "MNT_3_4") (pintype "passive"))
      (node (ref "J300") (pin "5") (pinfunction "MNT_4_5") (pintype "passive"))
      (node (ref "J301") (pin "2") (pinfunction "MNT_1_2") (pintype "passive"))
      (node (ref "J301") (pin "3") (pinfunction "MNT_2_3") (pintype "passive"))
      (node (ref "J301") (pin "4") (pinfunction "MNT_3_4") (pintype "passive"))
      (node (ref "J301") (pin "5") (pinfunction "MNT_4_5") (pintype "passive"))
      (node (ref "J302") (pin "2") (pinfunction "MNT_1_2") (pintype "passive"))
      (node (ref "J302") (pin "3") (pinfunction "MNT_2_3") (pintype "passive"))
      (node (ref "J302") (pin "4") (pinfunction "MNT_3_4") (pintype "passive"))
      (node (ref "J302") (pin "5") (pinfunction "MNT_4_5") (pintype "passive"))
      (node (ref "J303") (pin "2") (pinfunction "MNT_1_2") (pintype "passive"))
      (node (ref "J303") (pin "3") (pinfunction "MNT_2_3") (pintype "passive"))
      (node (ref "J303") (pin "4") (pinfunction "MNT_3_4") (pintype "passive"))
      (node (ref "J303") (pin "5") (pinfunction "MNT_4_5") (pintype "passive"))
      (node (ref "P300") (pin "5") (pinfunction "5_5") (pintype "passive"))
      (node (ref "P300") (pin "6") (pinfunction "6_6") (pintype "passive"))
      (node (ref "R300") (pin "1") (pinfunction "1_1") (pintype "passive"))
      (node (ref "R301") (pin "1") (pinfunction "1_1") (pintype "passive"))
      (node (ref "R308") (pin "1") (pinfunction "1_1") (pintype "passive"))
      (node (ref "R309") (pin "1") (pinfunction "1_1") (pintype "passive"))
      (node (ref "R310") (pin "1") (pinfunction "1_1") (pintype "passive"))
      (node (ref "R311") (pin "1") (pinfunction "1_1") (pintype "passive"))
      (node (ref "R312") (pin "1") (pinfunction "1_1") (pintype "passive"))
      (node (ref "SW300") (pin "2") (pinfunction "2_2") (pintype "passive"))
      (node (ref "SW300") (pin "3") (pinfunction "GND_3") (pintype "power_in"))
      (node (ref "SW300") (pin "4") (pinfunction "GND_4") (pintype "power_in"))
      (node (ref "SW301") (pin "2") (pinfunction "2_2") (pintype "passive"))
      (node (ref "SW301") (pin "3") (pinfunction "GND_3") (pintype "power_in"))
      (node (ref "SW301") (pin "4") (pinfunction "GND_4") (pintype "power_in"))
      (node (ref "SW302") (pin "2") (pinfunction "2_2") (pintype "passive"))
      (node (ref "SW302") (pin "3") (pinfunction "GND_3") (pintype "power_in"))
      (node (ref "SW302") (pin "4") (pinfunction "GND_4") (pintype "power_in"))
      (node (ref "U300") (pin "2") (pinfunction "GND_2") (pintype "power_in"))
      (node (ref "U301") (pin "2") (pinfunction "GND_2") (pintype "power_in"))
      (node (ref "U302") (pin "12") (pinfunction "VSSA_12") (pintype "power_in"))
      (node (ref "U302") (pin "18") (pinfunction "VSS_18") (pintype "power_in"))
      (node (ref "U302") (pin "63") (pinfunction "VSS_63") (pintype "power_in"))
      (node (ref "Y300") (pin "2") (pinfunction "GND_2") (pintype "power_in"))
      (node (ref "Y300") (pin "4") (pinfunction "GND_4") (pintype "power_in"))
    )
    (net (code "65") (name "Net-(C309-Pad1)") (class "Default")
      (node (ref "C309") (pin "1") (pinfunction "1_1") (pintype "passive"))
      (node (ref "R302") (pin "1") (pinfunction "1_1") (pintype "passive"))
      (node (ref "R305") (pin "2") (pinfunction "2_2") (pintype "passive"))
    )
    (net (code "66") (name "Net-(C310-Pad1)") (class "Default")
      (node (ref "C310") (pin "1") (pinfunction "1_1") (pintype "passive"))
      (node (ref "R303") (pin "1") (pinfunction "1_1") (pintype "passive"))
      (node (ref "R306") (pin "2") (pinfunction "2_2") (pintype "passive"))
    )
    (net (code "67") (name "Net-(C311-Pad1)") (class "Default")
      (node (ref "C311") (pin "1") (pinfunction "1_1") (pintype "passive"))
      (node (ref "R304") (pin "1") (pinfunction "1_1") (pintype "passive"))
      (node (ref "R307") (pin "2") (pinfunction "2_2") (pintype "passive"))
    )
    (net (code "68") (name "Net-(LD300-Pad2)") (class "Default")
      (node (ref "LD300") (pin "2") (pintype "passive"))
      (node (ref "R309") (pin "2") (pinfunction "2_2") (pintype "passive"))
    )
    (net (code "69") (name "Net-(LD300-Pad4)") (class "Default")
      (node (ref "LD300") (pin "4") (pintype "passive"))
      (node (ref "R310") (pin "2") (pinfunction "2_2") (pintype "passive"))
    )
    (net (code "70") (name "Net-(LD301-Pad2)") (class "Default")
      (node (ref "LD301") (pin "2") (pintype "passive"))
      (node (ref "R311") (pin "2") (pinfunction "2_2") (pintype "passive"))
    )
    (net (code "71") (name "Net-(LD301-Pad4)") (class "Default")
      (node (ref "LD301") (pin "4") (pintype "passive"))
      (node (ref "R312") (pin "2") (pinfunction "2_2") (pintype "passive"))
    )
    (net (code "72") (name "Net-(U302A-BOOT0)") (class "Default")
      (node (ref "R308") (pin "2") (pinfunction "2_2") (pintype "passive"))
      (node (ref "U302") (pin "60") (pinfunction "BOOT0_60") (pintype "input"))
    )
    (net (code "73") (name "unconnected-(P300-Pad3)") (class "Default")
      (node (ref "P300") (pin "3") (pinfunction "3_3") (pintype "passive+no_connect"))
    )
    (net (code "74") (name "unconnected-(U300-VREF-Pad5)") (class "Default")
      (node (ref "U300") (pin "5") (pinfunction "VREF_5") (pintype "output+no_connect"))
    )
    (net (code "75") (name "unconnected-(U301-VREF-Pad5)") (class "Default")
      (node (ref "U301") (pin "5") (pinfunction "VREF_5") (pintype "output+no_connect"))
    )
    (net (code "76") (name "unconnected-(U302A-PA1-Pad15)") (class "Default")
      (node (ref "U302") (pin "15") (pinfunction "PA1_15") (pintype "bidirectional+no_connect"))
    )
    (net (code "77") (name "unconnected-(U302A-PD2-Pad54)") (class "Default")
      (node (ref "U302") (pin "54") (pinfunction "PD2_54") (pintype "bidirectional+no_connect"))
    )
  )
)
